# 01-Antennas.net
KiCad netlist of a schematic drawn in Altium Designer
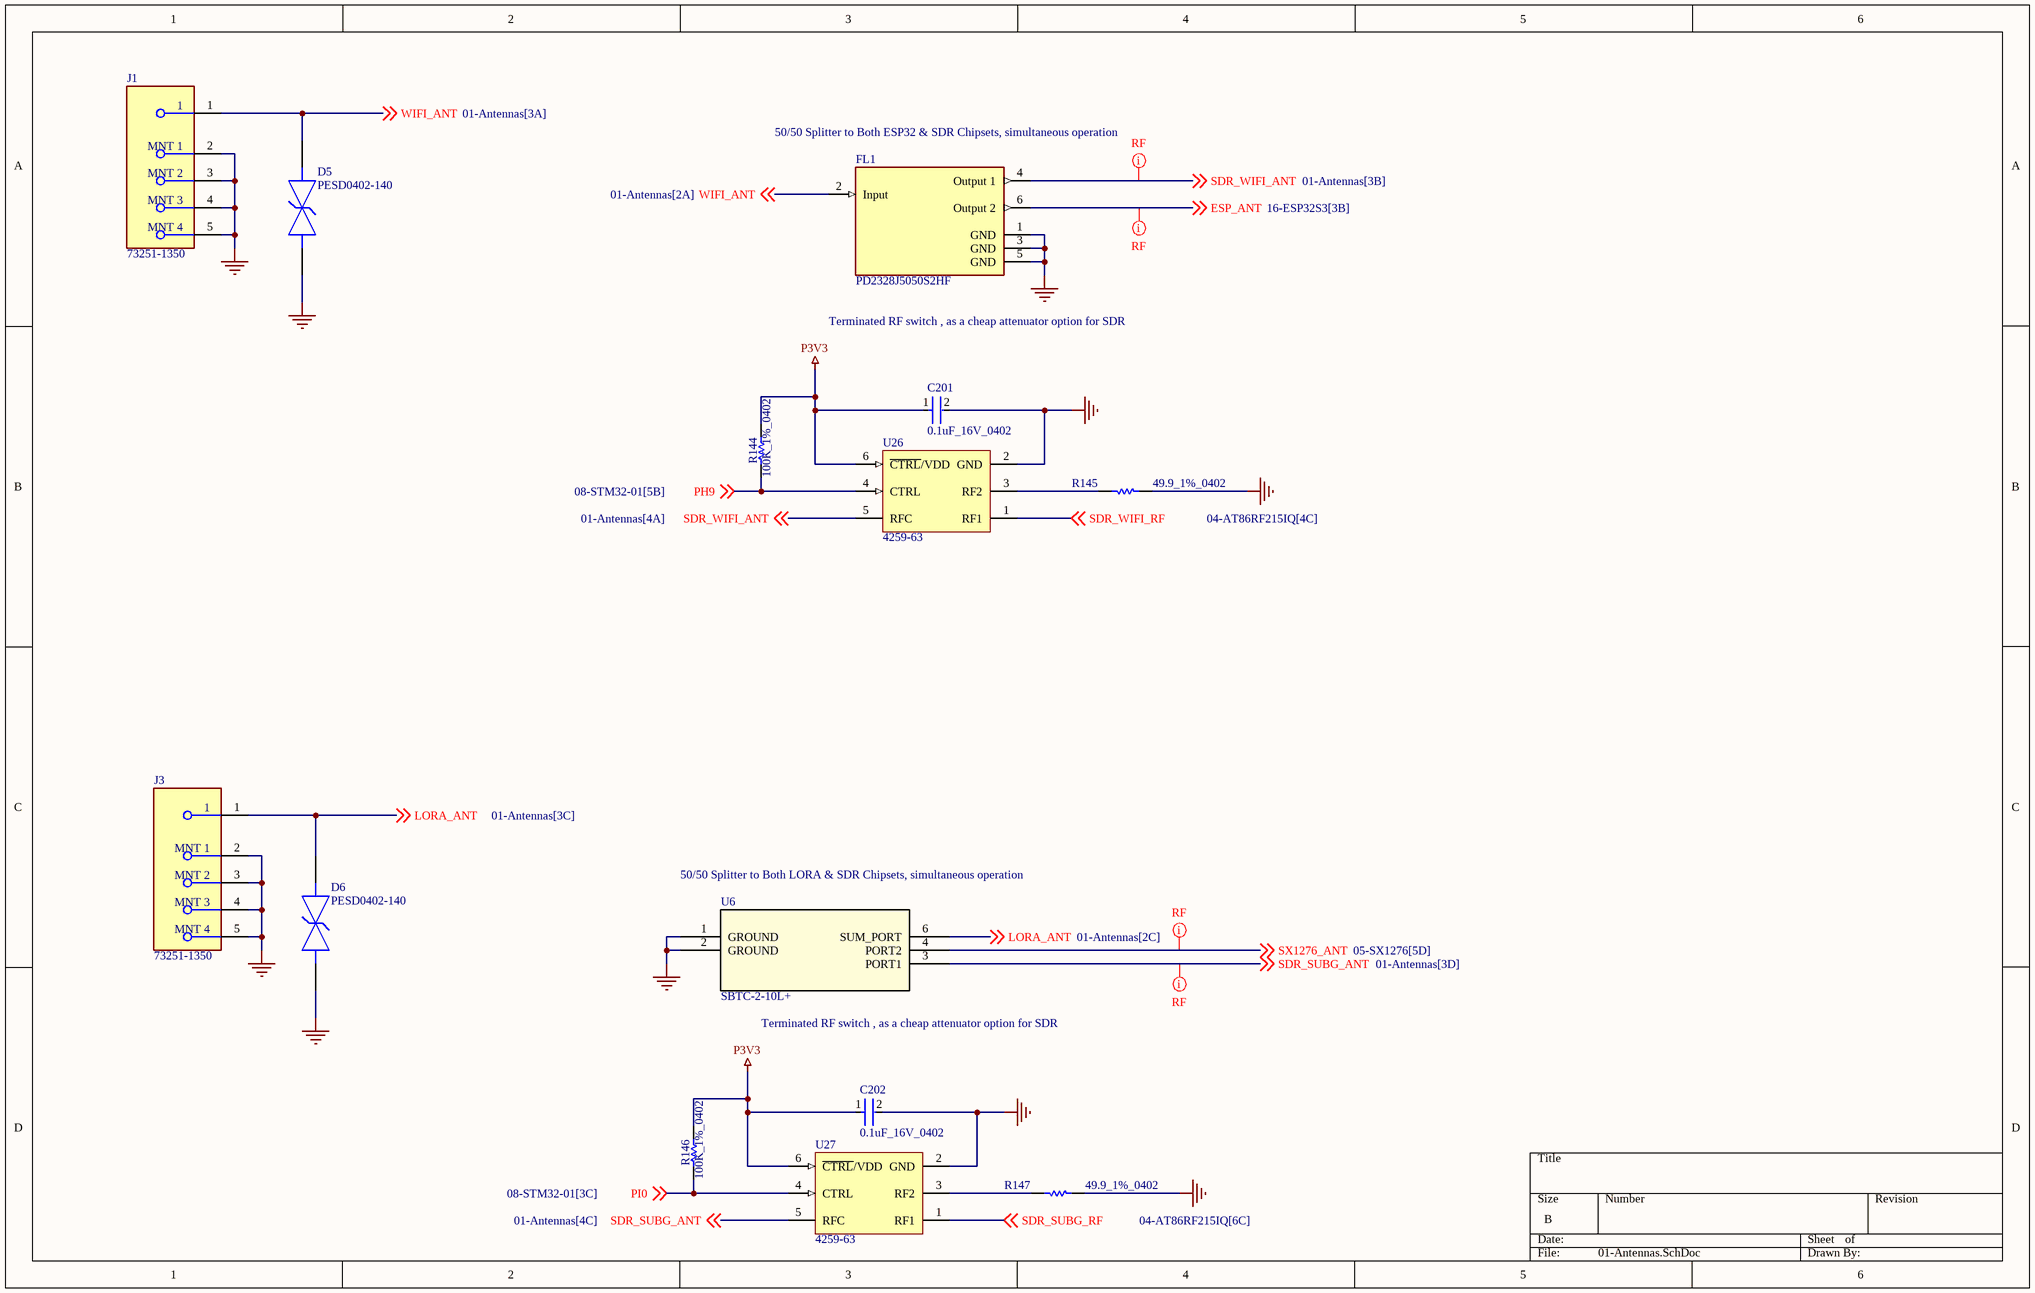
[diagram p0: 01-Antennas.SchDoc]

(export (version "E")
  (design (tool "Eeschema 10.0.6"))
  (components
    (comp (ref "C201")
      (value "0.1uF_16V_0402")
      (footprint "FP-C0402-BB-MFG")
      (description "CAP CER 0.1UF 16V 5% X7R 0402")
      (fields
        (field (name "MANUFACTURER") "Kemet")
        (field (name "MANUFACTURER PART NUMBER") "C0402C104J4RACTU")
      )
      (libsource (lib "Altium Content Vault") (part "b4654b650e69147ec39a6b967a45e02"))
    )
    (comp (ref "C202")
      (value "0.1uF_16V_0402")
      (footprint "FP-C0402-BB-MFG")
      (description "CAP CER 0.1UF 16V 5% X7R 0402")
      (fields
        (field (name "MANUFACTURER") "Kemet")
        (field (name "MANUFACTURER PART NUMBER") "C0402C104J4RACTU")
      )
      (libsource (lib "Altium Content Vault") (part "b4654b650e69147ec39a6b967a45e02"))
    )
    (comp (ref "D5")
      (value "PESD0402-140")
      (footprint "FP-PESD0402-MFG")
      (description "TVS DIODE 14V 40V 0402")
      (fields
        (field (name "OCTOPART") "https://octopart.com/pesd0402-140-littelfuse-74215061")
        (field (name "MANUFACTURER") "Littelfuse Inc.")
      )
      (libsource (lib "Altium Content Vault") (part "edccc070dd5cba1f9372128faf3915e"))
    )
    (comp (ref "D6")
      (value "PESD0402-140")
      (footprint "FP-PESD0402-MFG")
      (description "TVS DIODE 14V 40V 0402")
      (fields
        (field (name "OCTOPART") "https://octopart.com/pesd0402-140-littelfuse-74215061")
        (field (name "MANUFACTURER") "Littelfuse Inc.")
      )
      (libsource (lib "Altium Content Vault") (part "edccc070dd5cba1f9372128faf3915e"))
    )
    (comp (ref "FL1")
      (value "PD2328J5050S2HF")
      (footprint "FP-PD2328J5050S2HF-MFG")
      (description "RF POWER DVDR 2.3GHZ-2.8GHZ 0805")
      (libsource (lib "Altium Content Vault") (part "9911b460099a173dc6862ebc77257ed"))
    )
    (comp (ref "J1")
      (value "73251-1350")
      (footprint "FP-73251-1350-MFG")
      (description "CONN SMA JACK STR 50 OHM SMD")
      (fields
        (field (name "OCTOPART") "https://octopart.com/73251-1350-molex-5414390")
        (field (name "MANUFACTURER") "Molex")
      )
      (libsource (lib "Altium Content Vault") (part "474d33b8a96b1ade9ed6dd87a2b06d4"))
    )
    (comp (ref "J3")
      (value "73251-1350")
      (footprint "FP-73251-1350-MFG")
      (description "CONN SMA JACK STR 50 OHM SMD")
      (fields
        (field (name "OCTOPART") "https://octopart.com/73251-1350-molex-5414390")
        (field (name "MANUFACTURER") "Molex")
      )
      (libsource (lib "Altium Content Vault") (part "474d33b8a96b1ade9ed6dd87a2b06d4"))
    )
    (comp (ref "R144")
      (value "100K_1%_0402")
      (footprint "RESC1005X40X25ML05T10")
      (fields (field (name "MANUFACTURER") "Yageo") (field (name "PART NUMBER") "RC0402FR-13100KL"))
      (libsource (lib "Altium Content Vault") (part "RES"))
    )
    (comp (ref "R145")
      (value "49.9_1%_0402")
      (footprint "RESC1005X40X25NL10T10")
      (fields (field (name "PART NUMBER") "RK73H1ETTP49R9F") (field (name "MANUFACTURER") "KOA Speer"))
      (libsource (lib "Altium Content Vault") (part "RES"))
    )
    (comp (ref "R146")
      (value "100K_1%_0402")
      (footprint "RESC1005X40X25ML05T10")
      (fields (field (name "MANUFACTURER") "Yageo") (field (name "PART NUMBER") "RC0402FR-13100KL"))
      (libsource (lib "Altium Content Vault") (part "RES"))
    )
    (comp (ref "R147")
      (value "49.9_1%_0402")
      (footprint "RESC1005X40X25NL10T10")
      (fields (field (name "PART NUMBER") "RK73H1ETTP49R9F") (field (name "MANUFACTURER") "KOA Speer"))
      (libsource (lib "Altium Content Vault") (part "RES"))
    )
    (comp (ref "U6")
      (value "SBTC-2-10L+")
      (footprint "AT1029_MNC")
      (description "No Description Available")
      (fields (field (name "COPYRIGHT") "Copyright (C) 2023 Ultra Librarian. All rights reserved."))
      (libsource (lib "SBTC-2-10L&plus_") (part "SBTC-2-10L+"))
    )
    (comp (ref "U26")
      (value "4259-63")
      (footprint "PERE-SC-70-6_M")
      (description "IC RF Switch SPDT, 50 Ohm, 6-Pin SC70, RoHS, Tape and Reel")
      (fields (field (name "MANUFACTURER") "Peregrine Semiconductor"))
      (libsource (lib "Altium Content Vault") (part "PERE-PE4259-6"))
    )
    (comp (ref "U27")
      (value "4259-63")
      (footprint "PERE-SC-70-6_M")
      (description "IC RF Switch SPDT, 50 Ohm, 6-Pin SC70, RoHS, Tape and Reel")
      (fields (field (name "MANUFACTURER") "Peregrine Semiconductor"))
      (libsource (lib "Altium Content Vault") (part "PERE-PE4259-6"))
    )
  )
  (nets
    (net (code "1") (name "ESP_ANT") (class "Default")
      (node (ref "FL1") (pin "6") (pinfunction "Output_2_6") (pintype "output"))
    )
    (net (code "2") (name "GND") (class "Default")
      (node (ref "C201") (pin "2") (pinfunction "2_2") (pintype "passive"))
      (node (ref "C202") (pin "2") (pinfunction "2_2") (pintype "passive"))
      (node (ref "D5") (pin "1") (pinfunction "1_1") (pintype "passive"))
      (node (ref "D6") (pin "1") (pinfunction "1_1") (pintype "passive"))
      (node (ref "FL1") (pin "1") (pinfunction "GND_1") (pintype "power_in"))
      (node (ref "FL1") (pin "3") (pinfunction "GND_3") (pintype "power_in"))
      (node (ref "FL1") (pin "5") (pinfunction "GND_5") (pintype "power_in"))
      (node (ref "J1") (pin "2") (pinfunction "MNT_1_2") (pintype "passive"))
      (node (ref "J1") (pin "3") (pinfunction "MNT_2_3") (pintype "passive"))
      (node (ref "J1") (pin "4") (pinfunction "MNT_3_4") (pintype "passive"))
      (node (ref "J1") (pin "5") (pinfunction "MNT_4_5") (pintype "passive"))
      (node (ref "J3") (pin "2") (pinfunction "MNT_1_2") (pintype "passive"))
      (node (ref "J3") (pin "3") (pinfunction "MNT_2_3") (pintype "passive"))
      (node (ref "J3") (pin "4") (pinfunction "MNT_3_4") (pintype "passive"))
      (node (ref "J3") (pin "5") (pinfunction "MNT_4_5") (pintype "passive"))
      (node (ref "R145") (pin "2") (pinfunction "2_2") (pintype "passive"))
      (node (ref "R147") (pin "2") (pinfunction "2_2") (pintype "passive"))
      (node (ref "U26") (pin "2") (pinfunction "GND_2") (pintype "power_in"))
      (node (ref "U27") (pin "2") (pinfunction "GND_2") (pintype "power_in"))
      (node (ref "U6") (pin "1") (pinfunction "GROUND_1") (pintype "passive"))
      (node (ref "U6") (pin "2") (pinfunction "GROUND_2") (pintype "passive"))
    )
    (net (code "3") (name "LORA_ANT") (class "Default")
      (node (ref "D6") (pin "2") (pinfunction "2_2") (pintype "passive"))
      (node (ref "J3") (pin "1") (pinfunction "1_1") (pintype "passive"))
      (node (ref "U6") (pin "6") (pinfunction "SUM_PORT_6") (pintype "passive"))
    )
    (net (code "4") (name "Net-(U26-RF2)") (class "Default")
      (node (ref "R145") (pin "1") (pinfunction "1_1") (pintype "passive"))
      (node (ref "U26") (pin "3") (pinfunction "RF2_3") (pintype "passive"))
    )
    (net (code "5") (name "Net-(U27-RF2)") (class "Default")
      (node (ref "R147") (pin "1") (pinfunction "1_1") (pintype "passive"))
      (node (ref "U27") (pin "3") (pinfunction "RF2_3") (pintype "passive"))
    )
    (net (code "6") (name "P3V3") (class "Default")
      (node (ref "C201") (pin "1") (pinfunction "1_1") (pintype "passive"))
      (node (ref "C202") (pin "1") (pinfunction "1_1") (pintype "passive"))
      (node (ref "R144") (pin "2") (pinfunction "2_2") (pintype "passive"))
      (node (ref "R146") (pin "2") (pinfunction "2_2") (pintype "passive"))
      (node (ref "U26") (pin "6") (pinfunction "~{CTRL}/VDD_6") (pintype "input"))
      (node (ref "U27") (pin "6") (pinfunction "~{CTRL}/VDD_6") (pintype "input"))
    )
    (net (code "7") (name "PH9") (class "Default")
      (node (ref "R144") (pin "1") (pinfunction "1_1") (pintype "passive"))
      (node (ref "U26") (pin "4") (pinfunction "CTRL_4") (pintype "input"))
    )
    (net (code "8") (name "PI0") (class "Default")
      (node (ref "R146") (pin "1") (pinfunction "1_1") (pintype "passive"))
      (node (ref "U27") (pin "4") (pinfunction "CTRL_4") (pintype "input"))
    )
    (net (code "9") (name "SDR_SUBG_ANT") (class "Default")
      (node (ref "U27") (pin "5") (pinfunction "RFC_5") (pintype "passive"))
      (node (ref "U6") (pin "3") (pinfunction "PORT1_3") (pintype "passive"))
    )
    (net (code "10") (name "SDR_SUBG_RF") (class "Default")
      (node (ref "U27") (pin "1") (pinfunction "RF1_1") (pintype "passive"))
    )
    (net (code "11") (name "SDR_WIFI_ANT") (class "Default")
      (node (ref "FL1") (pin "4") (pinfunction "Output_1_4") (pintype "output"))
      (node (ref "U26") (pin "5") (pinfunction "RFC_5") (pintype "passive"))
    )
    (net (code "12") (name "SDR_WIFI_RF") (class "Default")
      (node (ref "U26") (pin "1") (pinfunction "RF1_1") (pintype "passive"))
    )
    (net (code "13") (name "SX1276_ANT") (class "Default")
      (node (ref "U6") (pin "4") (pinfunction "PORT2_4") (pintype "passive"))
    )
    (net (code "14") (name "WIFI_ANT") (class "Default")
      (node (ref "D5") (pin "2") (pinfunction "2_2") (pintype "passive"))
      (node (ref "FL1") (pin "2") (pinfunction "Input_2") (pintype "input"))
      (node (ref "J1") (pin "1") (pinfunction "1_1") (pintype "passive"))
    )
  )
)
